# SCH_WINGLET_PWR.net
KiCad netlist of a schematic drawn in Altium Designer
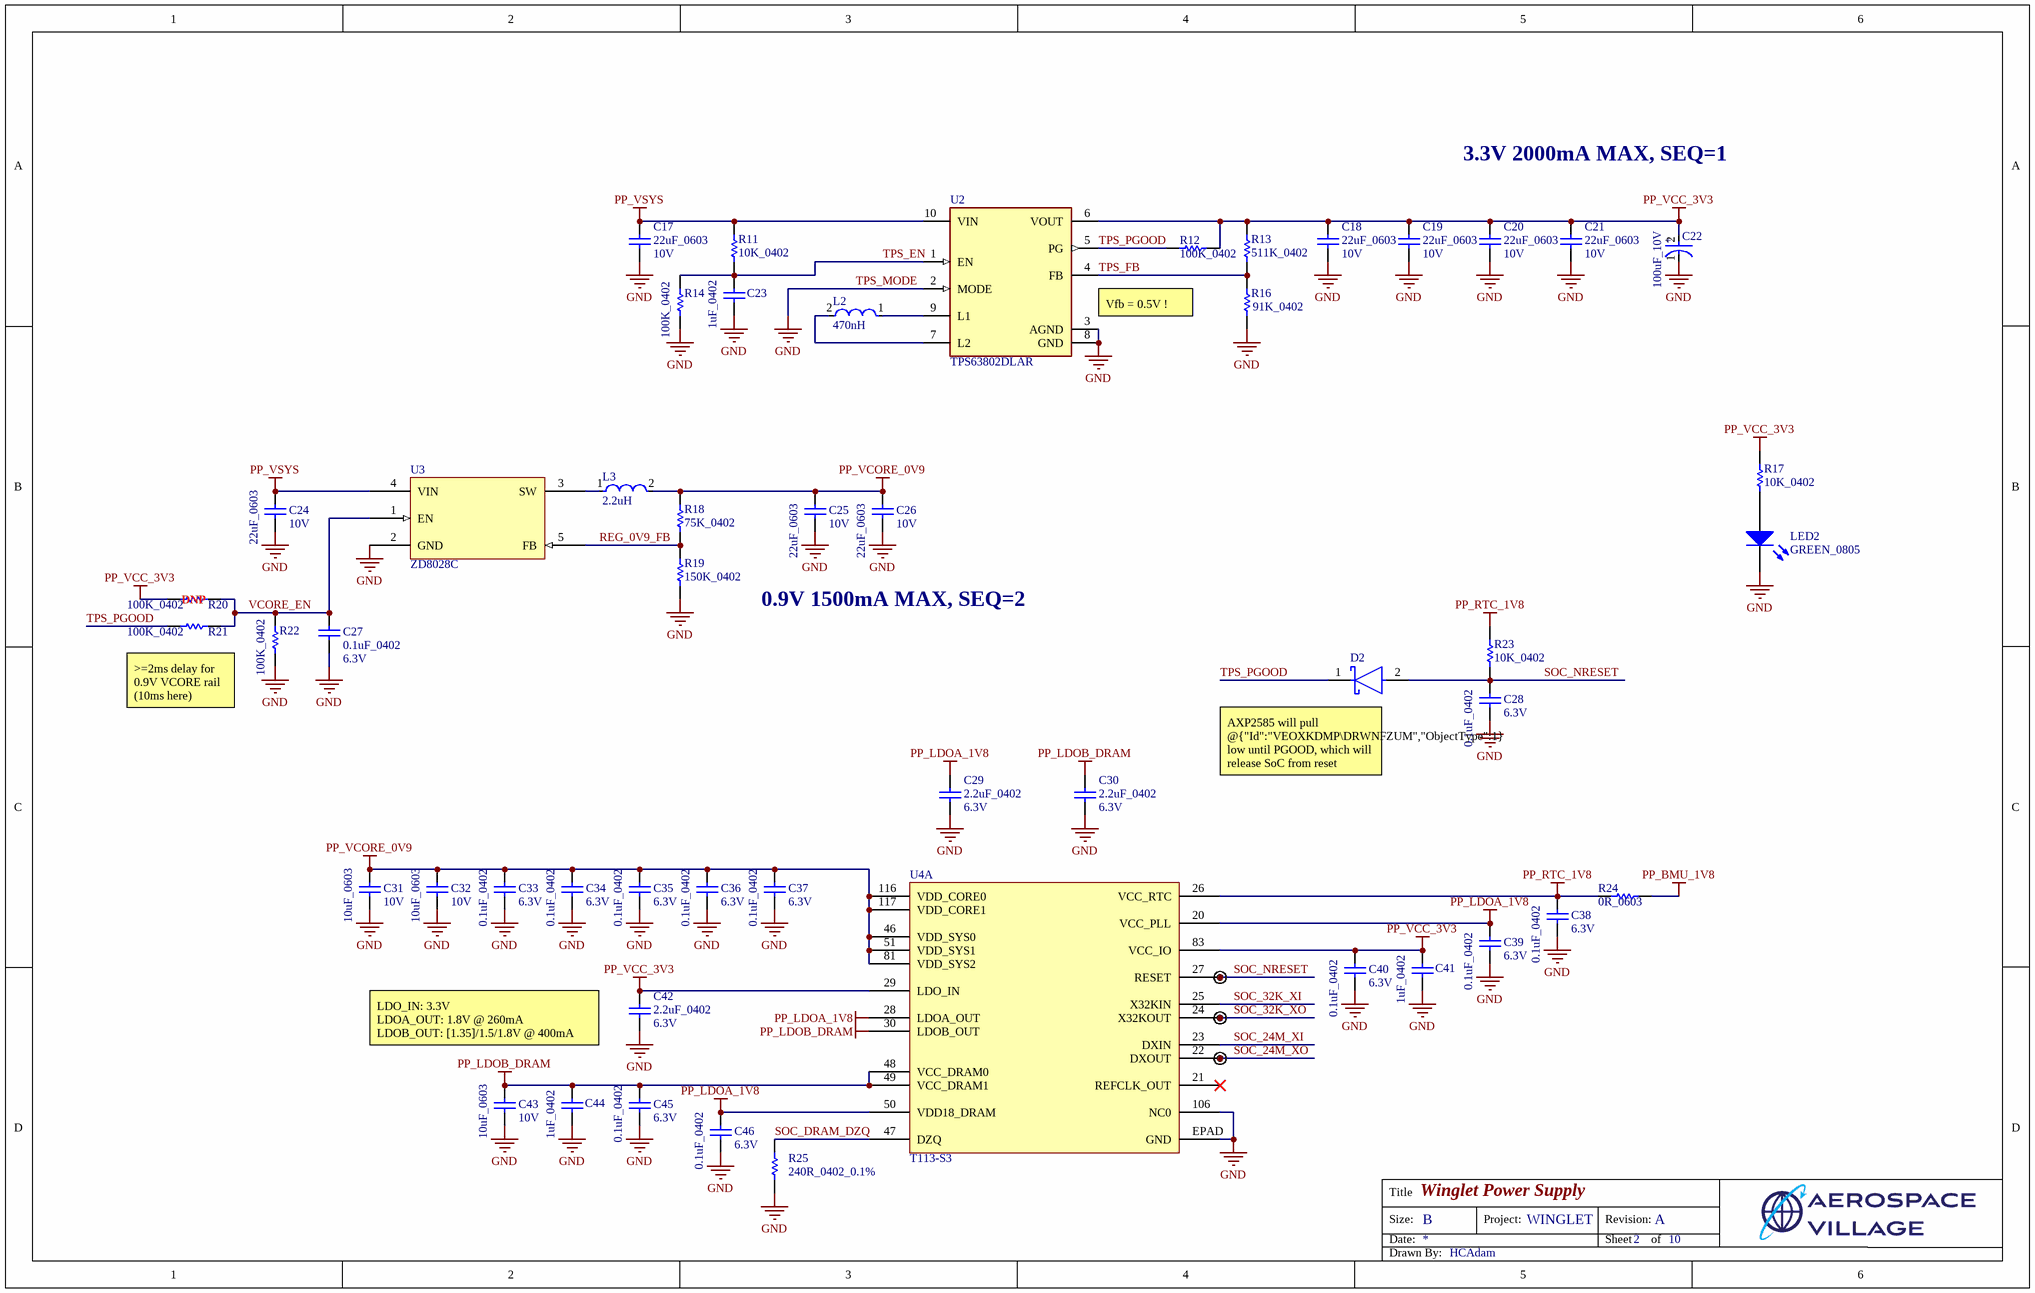
[diagram p0: SCH_WINGLET_PWR.SchDoc]

(export (version "E")
  (design (tool "Eeschema 10.0.6"))
  (components
    (comp (ref "C17")
      (value "22uF_0603")
      (footprint "CAPC1608X100X20NL10")
      (fields
        (field (name "MANUFACTURER") "TDK")
        (field (name "TOLERANCE") "±20%")
        (field (name "PCN PART NUMBER") "MLCCPartNumberChange30/Nov/2012")
        (field (name "VOLTAGE RATING") "10V")
      )
      (libsource (lib "Altium Content Vault") (part "CAP-NP-2"))
    )
    (comp (ref "C18")
      (value "22uF_0603")
      (footprint "CAPC1608X100X20NL10")
      (fields
        (field (name "MANUFACTURER") "TDK")
        (field (name "TOLERANCE") "±20%")
        (field (name "PCN PART NUMBER") "MLCCPartNumberChange30/Nov/2012")
        (field (name "VOLTAGE RATING") "10V")
      )
      (libsource (lib "Altium Content Vault") (part "CAP-NP-2"))
    )
    (comp (ref "C19")
      (value "22uF_0603")
      (footprint "CAPC1608X100X20NL10")
      (fields
        (field (name "MANUFACTURER") "TDK")
        (field (name "TOLERANCE") "±20%")
        (field (name "PCN PART NUMBER") "MLCCPartNumberChange30/Nov/2012")
        (field (name "VOLTAGE RATING") "10V")
      )
      (libsource (lib "Altium Content Vault") (part "CAP-NP-2"))
    )
    (comp (ref "C20")
      (value "22uF_0603")
      (footprint "CAPC1608X100X20NL10")
      (fields
        (field (name "MANUFACTURER") "TDK")
        (field (name "TOLERANCE") "±20%")
        (field (name "PCN PART NUMBER") "MLCCPartNumberChange30/Nov/2012")
        (field (name "VOLTAGE RATING") "10V")
      )
      (libsource (lib "Altium Content Vault") (part "CAP-NP-2"))
    )
    (comp (ref "C21")
      (value "22uF_0603")
      (footprint "CAPC1608X100X20NL10")
      (fields
        (field (name "MANUFACTURER") "TDK")
        (field (name "TOLERANCE") "±20%")
        (field (name "PCN PART NUMBER") "MLCCPartNumberChange30/Nov/2012")
        (field (name "VOLTAGE RATING") "10V")
      )
      (libsource (lib "Altium Content Vault") (part "CAP-NP-2"))
    )
    (comp (ref "C22")
      (value "100uF_10V")
      (footprint "FP-TAJB-MFG")
      (description "100uF 10V ±10% 1.7Ω SMD CASE-B (3528) Tantalum Capacitor")
      (fields (field (name "VOLTAGE") "6.3V") (field (name "TOLERANCE") "10%"))
      (libsource (lib "Altium Content Vault") (part "203bc49f2ac43e59fd269a8c329ed05"))
    )
    (comp (ref "C23")
      (value "1uF_0402")
      (footprint "CAPC1005X55X25NL5T10")
      (fields (field (name "TOLERANCE") "10%") (field (name "PARTNUMBER") "GRM155R60J105KE19D"))
      (libsource (lib "Altium Content Vault") (part "CAP-NP-2"))
    )
    (comp (ref "C24")
      (value "22uF_0603")
      (footprint "CAPC1608X100X20NL10")
      (fields
        (field (name "MANUFACTURER") "TDK")
        (field (name "TOLERANCE") "±20%")
        (field (name "PCN PART NUMBER") "MLCCPartNumberChange30/Nov/2012")
        (field (name "VOLTAGE RATING") "10V")
      )
      (libsource (lib "Altium Content Vault") (part "CAP-NP-2"))
    )
    (comp (ref "C25")
      (value "22uF_0603")
      (footprint "CAPC1608X100X20NL10")
      (fields
        (field (name "MANUFACTURER") "TDK")
        (field (name "TOLERANCE") "±20%")
        (field (name "PCN PART NUMBER") "MLCCPartNumberChange30/Nov/2012")
        (field (name "VOLTAGE RATING") "10V")
      )
      (libsource (lib "Altium Content Vault") (part "CAP-NP-2"))
    )
    (comp (ref "C26")
      (value "22uF_0603")
      (footprint "CAPC1608X100X20NL10")
      (fields
        (field (name "MANUFACTURER") "TDK")
        (field (name "TOLERANCE") "±20%")
        (field (name "PCN PART NUMBER") "MLCCPartNumberChange30/Nov/2012")
        (field (name "VOLTAGE RATING") "10V")
      )
      (libsource (lib "Altium Content Vault") (part "CAP-NP-2"))
    )
    (comp (ref "C27")
      (value "0.1uF_0402")
      (footprint "CAPC1005X56X25NL10T15")
      (description "04026D104KAT2A")
      (fields (field (name "MANUFACTURER") "AVX Interconnect / Elco") (field (name "VOLTAGE RATING") "6.3V"))
      (libsource (lib "Altium Content Vault") (part "CAP"))
    )
    (comp (ref "C28")
      (value "0.1uF_0402")
      (footprint "CAPC1005X56X25NL10T15")
      (description "04026D104KAT2A")
      (fields (field (name "MANUFACTURER") "AVX Interconnect / Elco") (field (name "VOLTAGE RATING") "6.3V"))
      (libsource (lib "Altium Content Vault") (part "CAP"))
    )
    (comp (ref "C29")
      (value "2.2uF_0402")
      (footprint "CAPC1005X55X25NL05T10")
      (description "GRM155R60J225ME15D")
      (fields (field (name "MANUFACTURER") "Murata") (field (name "VOLTAGE RATING") "6.3V"))
      (libsource (lib "Altium Content Vault") (part "CAP"))
    )
    (comp (ref "C30")
      (value "2.2uF_0402")
      (footprint "CAPC1005X55X25NL05T10")
      (description "GRM155R60J225ME15D")
      (fields (field (name "MANUFACTURER") "Murata") (field (name "VOLTAGE RATING") "6.3V"))
      (libsource (lib "Altium Content Vault") (part "CAP"))
    )
    (comp (ref "C31")
      (value "10uF_0603")
      (footprint "CAPC1609X100X15NL20")
      (fields
        (field (name "PART NUMBER") "TACL106M006XTA")
        (field (name "MANUFACTURER") "AVX Interconnect / Elco")
        (field (name "VOLTAGE RATING") "10V")
      )
      (libsource (lib "Altium Content Vault") (part "CAP"))
    )
    (comp (ref "C32")
      (value "10uF_0603")
      (footprint "CAPC1609X100X15NL20")
      (fields
        (field (name "PART NUMBER") "TACL106M006XTA")
        (field (name "MANUFACTURER") "AVX Interconnect / Elco")
        (field (name "VOLTAGE RATING") "10V")
      )
      (libsource (lib "Altium Content Vault") (part "CAP"))
    )
    (comp (ref "C33")
      (value "0.1uF_0402")
      (footprint "CAPC1005X56X25NL10T15")
      (description "04026D104KAT2A")
      (fields (field (name "MANUFACTURER") "AVX Interconnect / Elco") (field (name "VOLTAGE RATING") "6.3V"))
      (libsource (lib "Altium Content Vault") (part "CAP"))
    )
    (comp (ref "C34")
      (value "0.1uF_0402")
      (footprint "CAPC1005X56X25NL10T15")
      (description "04026D104KAT2A")
      (fields (field (name "MANUFACTURER") "AVX Interconnect / Elco") (field (name "VOLTAGE RATING") "6.3V"))
      (libsource (lib "Altium Content Vault") (part "CAP"))
    )
    (comp (ref "C35")
      (value "0.1uF_0402")
      (footprint "CAPC1005X56X25NL10T15")
      (description "04026D104KAT2A")
      (fields (field (name "MANUFACTURER") "AVX Interconnect / Elco") (field (name "VOLTAGE RATING") "6.3V"))
      (libsource (lib "Altium Content Vault") (part "CAP"))
    )
    (comp (ref "C36")
      (value "0.1uF_0402")
      (footprint "CAPC1005X56X25NL10T15")
      (description "04026D104KAT2A")
      (fields (field (name "MANUFACTURER") "AVX Interconnect / Elco") (field (name "VOLTAGE RATING") "6.3V"))
      (libsource (lib "Altium Content Vault") (part "CAP"))
    )
    (comp (ref "C37")
      (value "0.1uF_0402")
      (footprint "CAPC1005X56X25NL10T15")
      (description "04026D104KAT2A")
      (fields (field (name "MANUFACTURER") "AVX Interconnect / Elco") (field (name "VOLTAGE RATING") "6.3V"))
      (libsource (lib "Altium Content Vault") (part "CAP"))
    )
    (comp (ref "C38")
      (value "0.1uF_0402")
      (footprint "CAPC1005X56X25NL10T15")
      (description "04026D104KAT2A")
      (fields (field (name "MANUFACTURER") "AVX Interconnect / Elco") (field (name "VOLTAGE RATING") "6.3V"))
      (libsource (lib "Altium Content Vault") (part "CAP"))
    )
    (comp (ref "C39")
      (value "0.1uF_0402")
      (footprint "CAPC1005X56X25NL10T15")
      (description "04026D104KAT2A")
      (fields (field (name "MANUFACTURER") "AVX Interconnect / Elco") (field (name "VOLTAGE RATING") "6.3V"))
      (libsource (lib "Altium Content Vault") (part "CAP"))
    )
    (comp (ref "C40")
      (value "0.1uF_0402")
      (footprint "CAPC1005X56X25NL10T15")
      (description "04026D104KAT2A")
      (fields (field (name "MANUFACTURER") "AVX Interconnect / Elco") (field (name "VOLTAGE RATING") "6.3V"))
      (libsource (lib "Altium Content Vault") (part "CAP"))
    )
    (comp (ref "C41")
      (value "1uF_0402")
      (footprint "CAPC1005X55X25NL5T10")
      (fields (field (name "TOLERANCE") "10%") (field (name "PARTNUMBER") "GRM155R60J105KE19D"))
      (libsource (lib "Altium Content Vault") (part "CAP-NP-2"))
    )
    (comp (ref "C42")
      (value "2.2uF_0402")
      (footprint "CAPC1005X55X25NL05T10")
      (description "GRM155R60J225ME15D")
      (fields (field (name "MANUFACTURER") "Murata") (field (name "VOLTAGE RATING") "6.3V"))
      (libsource (lib "Altium Content Vault") (part "CAP"))
    )
    (comp (ref "C43")
      (value "10uF_0603")
      (footprint "CAPC1609X100X15NL20")
      (fields
        (field (name "PART NUMBER") "TACL106M006XTA")
        (field (name "MANUFACTURER") "AVX Interconnect / Elco")
        (field (name "VOLTAGE RATING") "10V")
      )
      (libsource (lib "Altium Content Vault") (part "CAP"))
    )
    (comp (ref "C44")
      (value "1uF_0402")
      (footprint "CAPC1005X55X25NL5T10")
      (fields (field (name "TOLERANCE") "10%") (field (name "PARTNUMBER") "GRM155R60J105KE19D"))
      (libsource (lib "Altium Content Vault") (part "CAP-NP-2"))
    )
    (comp (ref "C45")
      (value "0.1uF_0402")
      (footprint "CAPC1005X56X25NL10T15")
      (description "04026D104KAT2A")
      (fields (field (name "MANUFACTURER") "AVX Interconnect / Elco") (field (name "VOLTAGE RATING") "6.3V"))
      (libsource (lib "Altium Content Vault") (part "CAP"))
    )
    (comp (ref "C46")
      (value "0.1uF_0402")
      (footprint "CAPC1005X56X25NL10T15")
      (description "04026D104KAT2A")
      (fields (field (name "MANUFACTURER") "AVX Interconnect / Elco") (field (name "VOLTAGE RATING") "6.3V"))
      (libsource (lib "Altium Content Vault") (part "CAP"))
    )
    (comp (ref "D2")
      (value "BAT54KFILM")
      (footprint "FP-SOD-523-MFG")
      (description "DIODE SCHOTTKY 40V 300MA SOD523")
      (fields
        (field (name "OCTOPART") "https://octopart.com/bat54kfilm-stmicroelectronics-39618022")
        (field (name "MANUFACTURER") "STMicroelectronics")
      )
      (libsource (lib "Altium Content Vault") (part "1d6ec82d83fb6aee721767c19dac4b9"))
    )
    (comp (ref "L2")
      (value "470nH")
      (footprint "FP-DFE252012C-IPC_A")
      (description "Shielded Wirewound Inductor 0.47uH 20% 4000mA 0.027Ω 1008 (2520)\r\nDFE252012PD-R47M")
      (libsource (lib "Altium Content Vault") (part "725321dda6339637d4d059423bc1c3c"))
    )
    (comp (ref "L3")
      (value "2.2uH")
      (footprint "FP-NR3015-MFG")
      (description "SMD Power Inductors 2.2uH ±20% 1.48A 72mΩ\r\nNR3015T2R2M")
      (fields (field (name "TOLERANCE") "20%"))
      (libsource (lib "") (part "725321dda6339637d4d059423bc1c3c_1"))
    )
    (comp (ref "LED2")
      (value "GREEN_0805")
      (footprint "0805_A")
      (description "SMD mono-color Chip LED, WL-SMCW, Green\r\n150080GS75000")
      (fields (field (name "PARTNUMBER") "150080GS75000") (field (name "MANUFACTURER") "Wuerth Elektronik"))
      (libsource (lib "Altium Content Vault") (part "WE-LED_K1A2-2"))
    )
    (comp (ref "R11")
      (value "10K_0402")
      (footprint "RESC1005X40X25NL05T05")
      (fields (field (name "TOLERANCE") "1%") (field (name "MANUFACTURER") "Panasonic"))
      (libsource (lib "Altium Content Vault") (part "RES-2"))
    )
    (comp (ref "R12")
      (value "100K_0402")
      (footprint "RESC1005X40X25NL05T10")
      (description "RC0402FR-07100KL")
      (fields (field (name "MANUFACTURER") "Yageo / Phycomp"))
      (libsource (lib "Altium Content Vault") (part "RES"))
    )
    (comp (ref "R13")
      (value "511K_0402")
      (footprint "RESC1005X40X25NL05T10")
      (description "RC0402FR-07100KL")
      (fields (field (name "MANUFACTURER") "Yageo / Phycomp"))
      (libsource (lib "Altium Content Vault") (part "RES"))
    )
    (comp (ref "R14")
      (value "100K_0402")
      (footprint "RESC1005X40X25NL05T10")
      (description "RC0402FR-07100KL")
      (fields (field (name "MANUFACTURER") "Yageo / Phycomp"))
      (libsource (lib "Altium Content Vault") (part "RES"))
    )
    (comp (ref "R16")
      (value "91K_0402")
      (footprint "RESC1005X40X25NL05T10")
      (description "RC0402FR-07100KL")
      (fields (field (name "MANUFACTURER") "Yageo / Phycomp"))
      (libsource (lib "Altium Content Vault") (part "RES"))
    )
    (comp (ref "R17")
      (value "10K_0402")
      (footprint "RESC1005X40X25NL05T05")
      (fields (field (name "TOLERANCE") "1%") (field (name "MANUFACTURER") "Panasonic"))
      (libsource (lib "Altium Content Vault") (part "RES-2"))
    )
    (comp (ref "R18")
      (value "75K_0402")
      (footprint "RESC1005X40X25NL05T05")
      (fields (field (name "TOLERANCE") "1%") (field (name "MANUFACTURER") "Panasonic"))
      (libsource (lib "Altium Content Vault") (part "RES-2"))
    )
    (comp (ref "R19")
      (value "150K_0402")
      (footprint "RESC1005X40X25NL05T05")
      (description "RC0402FR-07150KL")
      (fields (field (name "TOLERANCE") "1%") (field (name "MANUFACTURER") "Panasonic"))
      (libsource (lib "Altium Content Vault") (part "RES-2"))
    )
    (comp (ref "R20")
      (value "100K_0402")
      (footprint "RESC1005X40X25NL05T10")
      (description "RC0402FR-07100KL")
      (fields (field (name "MANUFACTURER") "Yageo / Phycomp") (field (name "DNP") "DNP"))
      (libsource (lib "Altium Content Vault") (part "RES"))
    )
    (comp (ref "R21")
      (value "100K_0402")
      (footprint "RESC1005X40X25NL05T10")
      (description "RC0402FR-07100KL")
      (fields (field (name "MANUFACTURER") "Yageo / Phycomp"))
      (libsource (lib "Altium Content Vault") (part "RES"))
    )
    (comp (ref "R22")
      (value "100K_0402")
      (footprint "RESC1005X40X25NL05T10")
      (description "RC0402FR-07100KL")
      (fields (field (name "MANUFACTURER") "Yageo / Phycomp"))
      (libsource (lib "Altium Content Vault") (part "RES"))
    )
    (comp (ref "R23")
      (value "10K_0402")
      (footprint "RESC1005X40X25NL05T05")
      (fields (field (name "TOLERANCE") "1%") (field (name "MANUFACTURER") "Panasonic"))
      (libsource (lib "Altium Content Vault") (part "RES-2"))
    )
    (comp (ref "R24")
      (value "0R_0603")
      (footprint "RESC1608X55X25LL10T15")
      (description "RC0603JR-100RL")
      (fields (field (name "MANUFACTURER") "Yageo"))
      (libsource (lib "Altium Content Vault") (part "RES"))
    )
    (comp (ref "R25")
      (value "240R_0402_0.1%")
      (footprint "RESC1005X40X25NL05T05")
      (fields (field (name "TOLERANCE") "1%") (field (name "PARTNUMBER") "ERJ-2RKF2400X"))
      (libsource (lib "Altium Content Vault") (part "RES-2"))
    )
    (comp (ref "TP4")
      (value "TESTPOINT")
      (footprint "TESTPOINT-0.7MM-SINGLE-LAYER")
      (description "TESTPOINT SINGLE LAYER 0.7MM")
      (libsource (lib "DCAV32_WINGLET_SCHLIB") (part "TP_07"))
    )
    (comp (ref "TP5")
      (value "TESTPOINT")
      (footprint "TESTPOINT-0.7MM-SINGLE-LAYER")
      (description "TESTPOINT SINGLE LAYER 0.7MM")
      (libsource (lib "DCAV32_WINGLET_SCHLIB") (part "TP_07"))
    )
    (comp (ref "TP6")
      (value "TESTPOINT")
      (footprint "TESTPOINT-0.7MM-SINGLE-LAYER")
      (description "TESTPOINT SINGLE LAYER 0.7MM")
      (libsource (lib "DCAV32_WINGLET_SCHLIB") (part "TP_07"))
    )
    (comp (ref "U2")
      (value "TPS63802DLAR")
      (footprint "FP-DLA0010A-MFG")
      (description "IC POWER MANAGEMENT")
      (fields
        (field (name "OCTOPART") "https://octopart.com/tps63802dlar-texas+instruments-97359678")
        (field (name "MANUFACTURER") "Texas Instruments")
      )
      (libsource (lib "Altium Content Vault") (part "f9a6115c6bf72e8ba457236a565d59e"))
    )
    (comp (ref "U3")
      (value "ZD8028C")
      (footprint "SOT95P292X115-5N")
      (description "1.5A 2MHz 5.5V Synchronous Buck Converter")
      (libsource (lib "DCAV32_WINGLET_SCHLIB") (part "ZD8028C"))
    )
    (comp (ref "U4")
      (value "T113-S3")
      (footprint "TSQFP40P1600X1600X160_HS-129N")
      (description "Allwinner Dual-core ARM Cortex-A7 Smart Control and Display SoC")
      (libsource (lib "DCAV32_WINGLET_SCHLIB") (part "T113-S3"))
    )
  )
  (nets
    (net (code "1") (name "/REG_0V9_FB") (class "Default")
      (node (ref "R18") (pin "1") (pinfunction "1_1") (pintype "passive"))
      (node (ref "R19") (pin "2") (pinfunction "2_2") (pintype "passive"))
      (node (ref "U3") (pin "5") (pinfunction "FB_5") (pintype "input"))
    )
    (net (code "2") (name "/SOC_24M_XI") (class "Default")
      (node (ref "U4") (pin "23") (pinfunction "DXIN_23") (pintype "passive"))
    )
    (net (code "3") (name "/SOC_24M_XO") (class "Default")
      (node (ref "TP6") (pin "1") (pinfunction "1_1") (pintype "passive"))
      (node (ref "U4") (pin "22") (pinfunction "DXOUT_22") (pintype "passive"))
    )
    (net (code "4") (name "/SOC_32K_XI") (class "Default")
      (node (ref "U4") (pin "25") (pinfunction "X32KIN_25") (pintype "passive"))
    )
    (net (code "5") (name "/SOC_32K_XO") (class "Default")
      (node (ref "TP5") (pin "1") (pinfunction "1_1") (pintype "passive"))
      (node (ref "U4") (pin "24") (pinfunction "X32KOUT_24") (pintype "passive"))
    )
    (net (code "6") (name "/SOC_DRAM_DZQ") (class "Default")
      (node (ref "R25") (pin "2") (pinfunction "2_2") (pintype "passive"))
      (node (ref "U4") (pin "47") (pinfunction "DZQ_47") (pintype "passive"))
    )
    (net (code "7") (name "/SOC_NRESET") (class "Default")
      (node (ref "C28") (pin "2") (pinfunction "2_2") (pintype "passive"))
      (node (ref "D2") (pin "2") (pinfunction "A_2") (pintype "passive"))
      (node (ref "R23") (pin "1") (pinfunction "1_1") (pintype "passive"))
      (node (ref "TP4") (pin "1") (pinfunction "1_1") (pintype "passive"))
      (node (ref "U4") (pin "27") (pinfunction "RESET_27") (pintype "passive"))
    )
    (net (code "8") (name "/TPS_EN") (class "Default")
      (node (ref "C23") (pin "2") (pinfunction "2_2") (pintype "passive"))
      (node (ref "R11") (pin "2") (pinfunction "2_2") (pintype "passive"))
      (node (ref "R14") (pin "1") (pinfunction "1_1") (pintype "passive"))
      (node (ref "U2") (pin "1") (pinfunction "EN_1") (pintype "input"))
    )
    (net (code "9") (name "/TPS_FB") (class "Default")
      (node (ref "R13") (pin "2") (pinfunction "2_2") (pintype "passive"))
      (node (ref "R16") (pin "1") (pinfunction "1_1") (pintype "passive"))
      (node (ref "U2") (pin "4") (pinfunction "FB_4") (pintype "passive"))
    )
    (net (code "10") (name "/TPS_PGOOD") (class "Default")
      (node (ref "D2") (pin "1") (pinfunction "C_1") (pintype "passive"))
      (node (ref "R12") (pin "1") (pinfunction "1_1") (pintype "passive"))
      (node (ref "R21") (pin "2") (pinfunction "2_2") (pintype "passive"))
      (node (ref "U2") (pin "5") (pinfunction "PG_5") (pintype "output"))
    )
    (net (code "11") (name "/VCORE_EN") (class "Default")
      (node (ref "C27") (pin "2") (pinfunction "2_2") (pintype "passive"))
      (node (ref "R20") (pin "1") (pinfunction "1_1") (pintype "passive"))
      (node (ref "R21") (pin "1") (pinfunction "1_1") (pintype "passive"))
      (node (ref "R22") (pin "1") (pinfunction "1_1") (pintype "passive"))
      (node (ref "U3") (pin "1") (pinfunction "EN_1") (pintype "input"))
    )
    (net (code "12") (name "GND") (class "Default")
      (node (ref "C17") (pin "1") (pinfunction "1_1") (pintype "passive"))
      (node (ref "C18") (pin "1") (pinfunction "1_1") (pintype "passive"))
      (node (ref "C19") (pin "1") (pinfunction "1_1") (pintype "passive"))
      (node (ref "C20") (pin "1") (pinfunction "1_1") (pintype "passive"))
      (node (ref "C21") (pin "1") (pinfunction "1_1") (pintype "passive"))
      (node (ref "C22") (pin "1") (pinfunction "C_1") (pintype "passive"))
      (node (ref "C23") (pin "1") (pinfunction "1_1") (pintype "passive"))
      (node (ref "C24") (pin "1") (pinfunction "1_1") (pintype "passive"))
      (node (ref "C25") (pin "1") (pinfunction "1_1") (pintype "passive"))
      (node (ref "C26") (pin "1") (pinfunction "1_1") (pintype "passive"))
      (node (ref "C27") (pin "1") (pinfunction "1_1") (pintype "passive"))
      (node (ref "C28") (pin "1") (pinfunction "1_1") (pintype "passive"))
      (node (ref "C29") (pin "1") (pinfunction "1_1") (pintype "passive"))
      (node (ref "C30") (pin "1") (pinfunction "1_1") (pintype "passive"))
      (node (ref "C31") (pin "1") (pinfunction "1_1") (pintype "passive"))
      (node (ref "C32") (pin "1") (pinfunction "1_1") (pintype "passive"))
      (node (ref "C33") (pin "1") (pinfunction "1_1") (pintype "passive"))
      (node (ref "C34") (pin "1") (pinfunction "1_1") (pintype "passive"))
      (node (ref "C35") (pin "1") (pinfunction "1_1") (pintype "passive"))
      (node (ref "C36") (pin "1") (pinfunction "1_1") (pintype "passive"))
      (node (ref "C37") (pin "1") (pinfunction "1_1") (pintype "passive"))
      (node (ref "C38") (pin "1") (pinfunction "1_1") (pintype "passive"))
      (node (ref "C39") (pin "1") (pinfunction "1_1") (pintype "passive"))
      (node (ref "C40") (pin "1") (pinfunction "1_1") (pintype "passive"))
      (node (ref "C41") (pin "1") (pinfunction "1_1") (pintype "passive"))
      (node (ref "C42") (pin "1") (pinfunction "1_1") (pintype "passive"))
      (node (ref "C43") (pin "1") (pinfunction "1_1") (pintype "passive"))
      (node (ref "C44") (pin "1") (pinfunction "1_1") (pintype "passive"))
      (node (ref "C45") (pin "1") (pinfunction "1_1") (pintype "passive"))
      (node (ref "C46") (pin "1") (pinfunction "1_1") (pintype "passive"))
      (node (ref "LED2") (pin "1") (pinfunction "K_1") (pintype "passive"))
      (node (ref "R14") (pin "2") (pinfunction "2_2") (pintype "passive"))
      (node (ref "R16") (pin "2") (pinfunction "2_2") (pintype "passive"))
      (node (ref "R19") (pin "1") (pinfunction "1_1") (pintype "passive"))
      (node (ref "R22") (pin "2") (pinfunction "2_2") (pintype "passive"))
      (node (ref "R25") (pin "1") (pinfunction "1_1") (pintype "passive"))
      (node (ref "U2") (pin "2") (pinfunction "MODE_2") (pintype "input"))
      (node (ref "U2") (pin "3") (pinfunction "AGND_3") (pintype "power_in"))
      (node (ref "U2") (pin "8") (pinfunction "GND_8") (pintype "power_in"))
      (node (ref "U3") (pin "2") (pinfunction "GND_2") (pintype "passive"))
      (node (ref "U4") (pin "106") (pinfunction "NC0_106") (pintype "passive"))
      (node (ref "U4") (pin "EPAD") (pinfunction "GND_EPAD") (pintype "passive"))
    )
    (net (code "13") (name "Net-(LED2-A)") (class "Default")
      (node (ref "LED2") (pin "2") (pinfunction "A_2") (pintype "passive"))
      (node (ref "R17") (pin "1") (pinfunction "1_1") (pintype "passive"))
    )
    (net (code "14") (name "Net-(U2-L1)") (class "Default")
      (node (ref "L2") (pin "1") (pinfunction "1_1") (pintype "passive"))
      (node (ref "U2") (pin "9") (pinfunction "L1_9") (pintype "passive"))
    )
    (net (code "15") (name "Net-(U2-L2)") (class "Default")
      (node (ref "L2") (pin "2") (pinfunction "2_2") (pintype "passive"))
      (node (ref "U2") (pin "7") (pinfunction "L2_7") (pintype "passive"))
    )
    (net (code "16") (name "Net-(U3-SW)") (class "Default")
      (node (ref "L3") (pin "1") (pinfunction "1_1") (pintype "passive"))
      (node (ref "U3") (pin "3") (pinfunction "SW_3") (pintype "passive"))
    )
    (net (code "17") (name "PP_BMU_1V8") (class "Default")
      (node (ref "R24") (pin "2") (pinfunction "2_2") (pintype "passive"))
    )
    (net (code "18") (name "PP_LDOA_1V8") (class "Default")
      (node (ref "C29") (pin "2") (pinfunction "2_2") (pintype "passive"))
      (node (ref "C39") (pin "2") (pinfunction "2_2") (pintype "passive"))
      (node (ref "C46") (pin "2") (pinfunction "2_2") (pintype "passive"))
      (node (ref "U4") (pin "20") (pinfunction "VCC_PLL_20") (pintype "passive"))
      (node (ref "U4") (pin "28") (pinfunction "LDOA_OUT_28") (pintype "passive"))
      (node (ref "U4") (pin "50") (pinfunction "VDD18_DRAM_50") (pintype "passive"))
    )
    (net (code "19") (name "PP_LDOB_DRAM") (class "Default")
      (node (ref "C30") (pin "2") (pinfunction "2_2") (pintype "passive"))
      (node (ref "C43") (pin "2") (pinfunction "2_2") (pintype "passive"))
      (node (ref "C44") (pin "2") (pinfunction "2_2") (pintype "passive"))
      (node (ref "C45") (pin "2") (pinfunction "2_2") (pintype "passive"))
      (node (ref "U4") (pin "30") (pinfunction "LDOB_OUT_30") (pintype "passive"))
      (node (ref "U4") (pin "48") (pinfunction "VCC_DRAM0_48") (pintype "passive"))
      (node (ref "U4") (pin "49") (pinfunction "VCC_DRAM1_49") (pintype "passive"))
    )
    (net (code "20") (name "PP_RTC_1V8") (class "Default")
      (node (ref "C38") (pin "2") (pinfunction "2_2") (pintype "passive"))
      (node (ref "R23") (pin "2") (pinfunction "2_2") (pintype "passive"))
      (node (ref "R24") (pin "1") (pinfunction "1_1") (pintype "passive"))
      (node (ref "U4") (pin "26") (pinfunction "VCC_RTC_26") (pintype "passive"))
    )
    (net (code "21") (name "PP_VCC_3V3") (class "Default")
      (node (ref "C18") (pin "2") (pinfunction "2_2") (pintype "passive"))
      (node (ref "C19") (pin "2") (pinfunction "2_2") (pintype "passive"))
      (node (ref "C20") (pin "2") (pinfunction "2_2") (pintype "passive"))
      (node (ref "C21") (pin "2") (pinfunction "2_2") (pintype "passive"))
      (node (ref "C22") (pin "2") (pinfunction "A_2") (pintype "passive"))
      (node (ref "C40") (pin "2") (pinfunction "2_2") (pintype "passive"))
      (node (ref "C41") (pin "2") (pinfunction "2_2") (pintype "passive"))
      (node (ref "C42") (pin "2") (pinfunction "2_2") (pintype "passive"))
      (node (ref "R12") (pin "2") (pinfunction "2_2") (pintype "passive"))
      (node (ref "R13") (pin "1") (pinfunction "1_1") (pintype "passive"))
      (node (ref "R17") (pin "2") (pinfunction "2_2") (pintype "passive"))
      (node (ref "R20") (pin "2") (pinfunction "2_2") (pintype "passive"))
      (node (ref "U2") (pin "6") (pinfunction "VOUT_6") (pintype "power_in"))
      (node (ref "U4") (pin "29") (pinfunction "LDO_IN_29") (pintype "passive"))
      (node (ref "U4") (pin "83") (pinfunction "VCC_IO_83") (pintype "passive"))
    )
    (net (code "22") (name "PP_VCORE_0V9") (class "Default")
      (node (ref "C25") (pin "2") (pinfunction "2_2") (pintype "passive"))
      (node (ref "C26") (pin "2") (pinfunction "2_2") (pintype "passive"))
      (node (ref "C31") (pin "2") (pinfunction "2_2") (pintype "passive"))
      (node (ref "C32") (pin "2") (pinfunction "2_2") (pintype "passive"))
      (node (ref "C33") (pin "2") (pinfunction "2_2") (pintype "passive"))
      (node (ref "C34") (pin "2") (pinfunction "2_2") (pintype "passive"))
      (node (ref "C35") (pin "2") (pinfunction "2_2") (pintype "passive"))
      (node (ref "C36") (pin "2") (pinfunction "2_2") (pintype "passive"))
      (node (ref "C37") (pin "2") (pinfunction "2_2") (pintype "passive"))
      (node (ref "L3") (pin "2") (pinfunction "2_2") (pintype "passive"))
      (node (ref "R18") (pin "2") (pinfunction "2_2") (pintype "passive"))
      (node (ref "U4") (pin "116") (pinfunction "VDD_CORE0_116") (pintype "passive"))
      (node (ref "U4") (pin "117") (pinfunction "VDD_CORE1_117") (pintype "passive"))
      (node (ref "U4") (pin "46") (pinfunction "VDD_SYS0_46") (pintype "passive"))
      (node (ref "U4") (pin "51") (pinfunction "VDD_SYS1_51") (pintype "passive"))
      (node (ref "U4") (pin "81") (pinfunction "VDD_SYS2_81") (pintype "passive"))
    )
    (net (code "23") (name "PP_VSYS") (class "Default")
      (node (ref "C17") (pin "2") (pinfunction "2_2") (pintype "passive"))
      (node (ref "C24") (pin "2") (pinfunction "2_2") (pintype "passive"))
      (node (ref "R11") (pin "1") (pinfunction "1_1") (pintype "passive"))
      (node (ref "U2") (pin "10") (pinfunction "VIN_10") (pintype "power_in"))
      (node (ref "U3") (pin "4") (pinfunction "VIN_4") (pintype "passive"))
    )
    (net (code "24") (name "unconnected-(U4A-REFCLK_OUT-Pad21)") (class "Default")
      (node (ref "U4") (pin "21") (pinfunction "REFCLK_OUT_21") (pintype "passive+no_connect"))
    )
  )
)
